# FPGAPower.net
KiCad netlist of a schematic drawn in Altium Designer
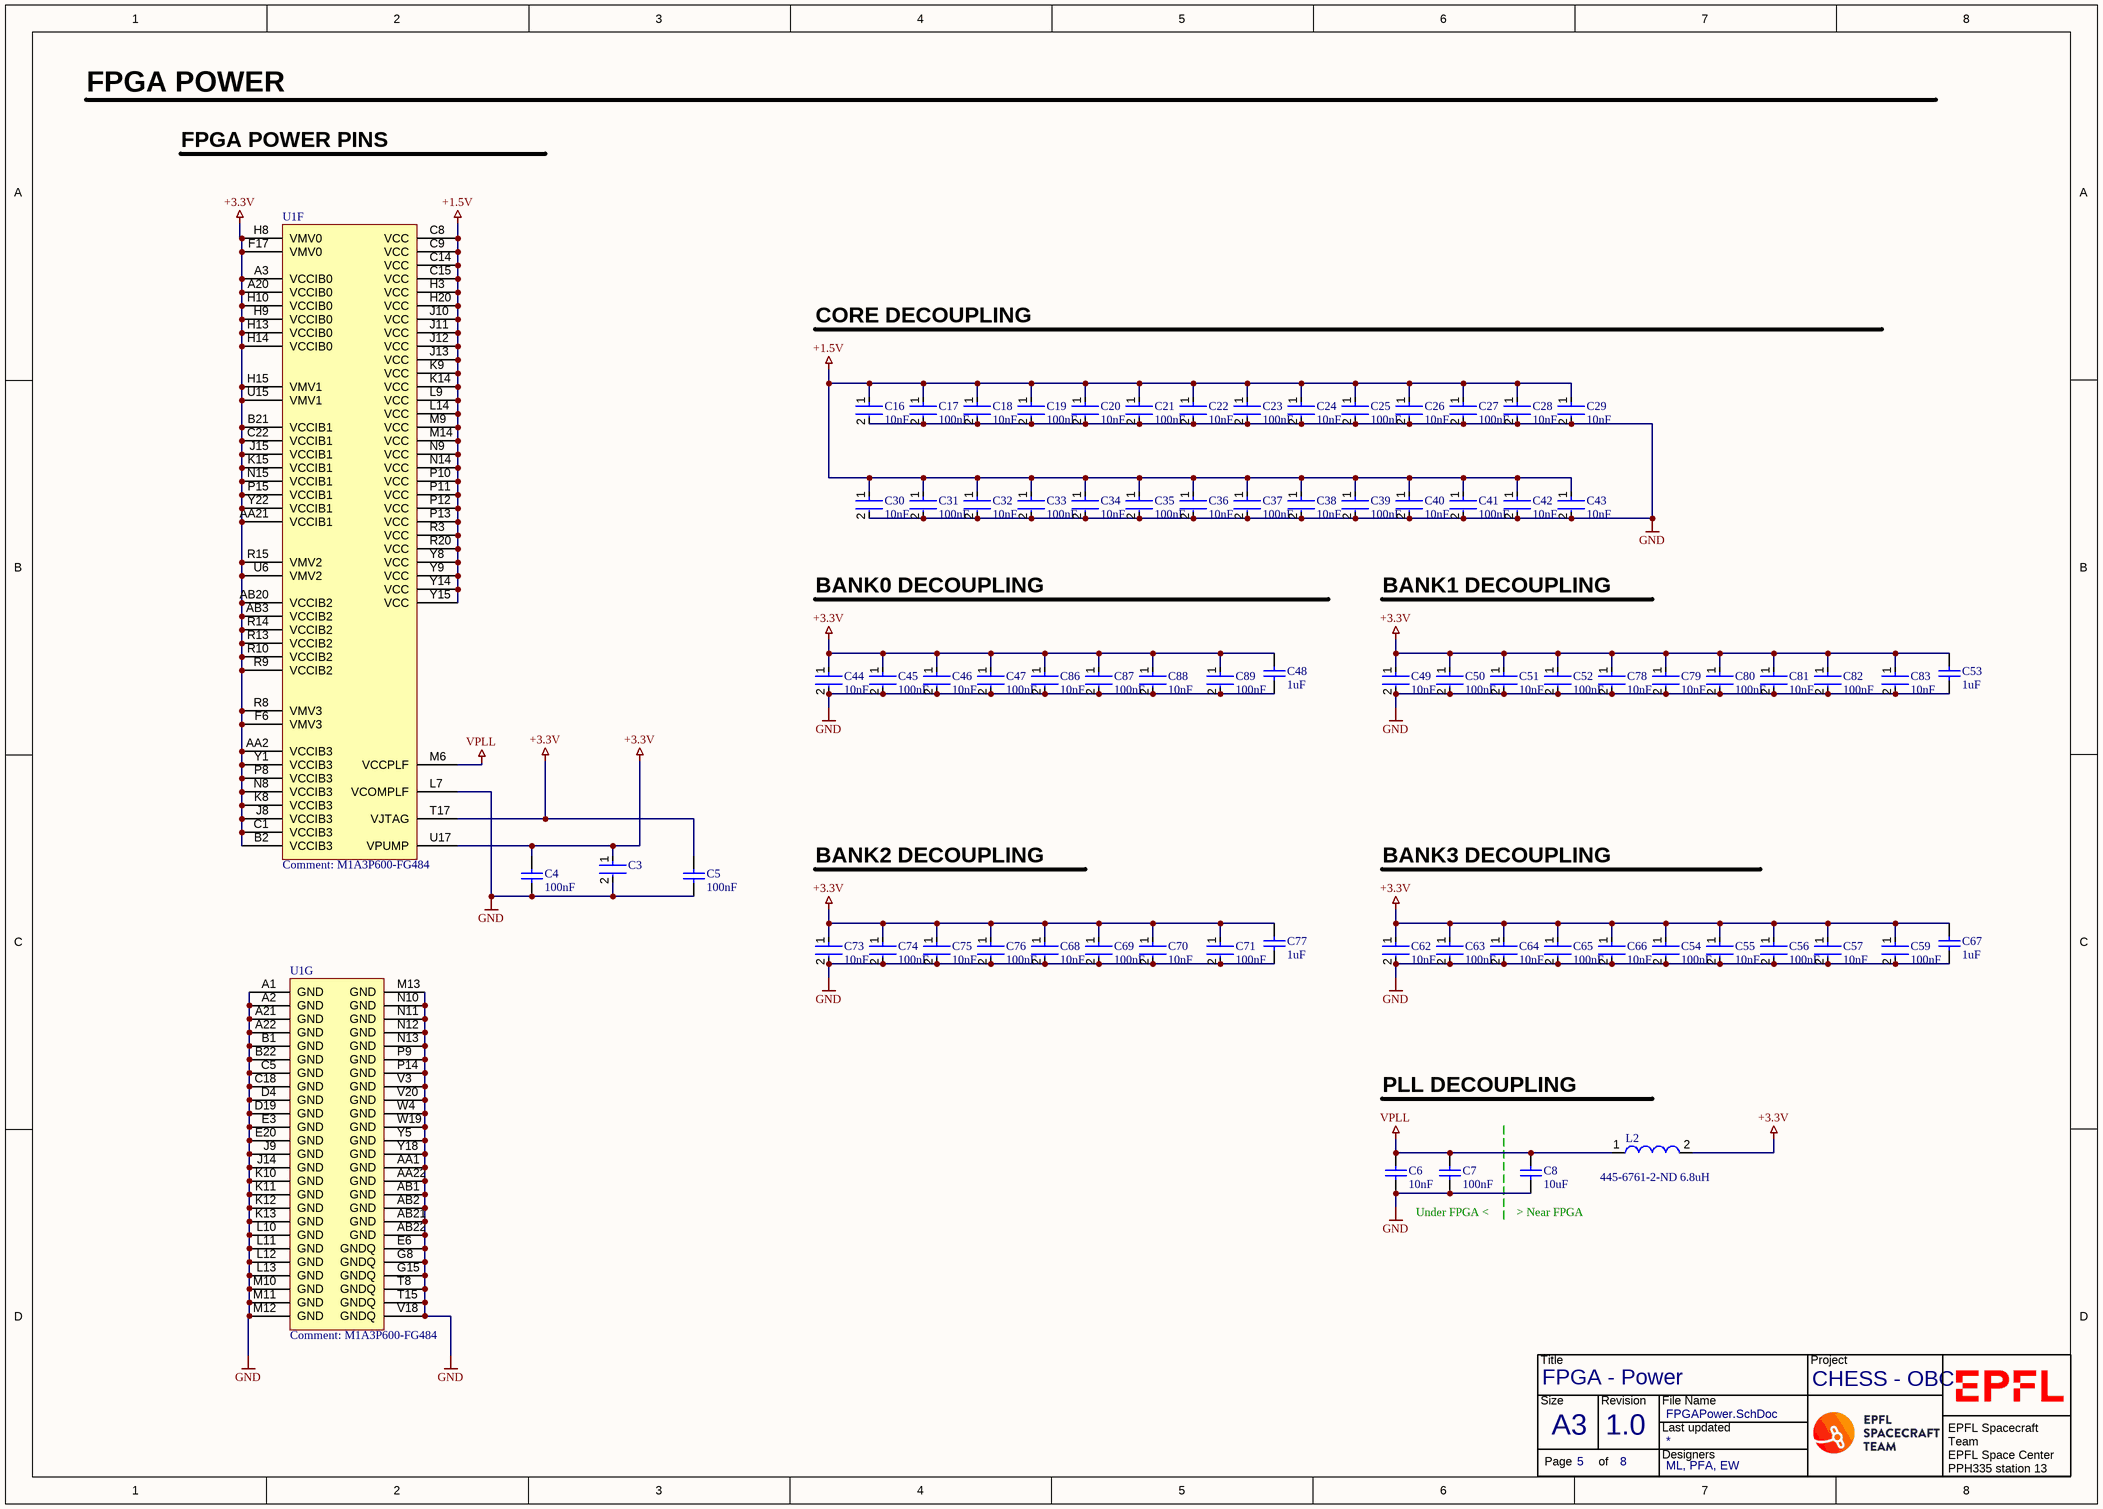
[diagram p0: FPGAPower.SchDoc]

(export (version "E")
  (design (tool "Eeschema 10.0.6"))
  (components
    (comp (ref "C3")
      (value "CC0402KRX5R6BB334")
      (footprint "FP-CC0402-MFG")
      (description "CAP CER 0.33UF 10V X5R 0402")
      (fields
        (field (name "MANUFACTURER") "YAGEO")
        (field (name "OCTOPART") "https://octopart.com/cc0402krx5r6bb334-yageo-21548561")
      )
      (libsource (lib "Altium Content Vault") (part "11868f565c42a9108669ba33697ecf6"))
    )
    (comp (ref "C4")
      (value "100nF")
      (footprint "CAPC1005X60X30ML05T10")
      (fields (field (name "MANUFACTURER") "Kemet") (field (name "PART NUMBER") "C0402C104K8PACTU"))
      (libsource (lib "Altium Content Vault") (part "CAP"))
    )
    (comp (ref "C5")
      (value "100nF")
      (footprint "CAPC1005X60X30ML05T10")
      (fields (field (name "MANUFACTURER") "Kemet") (field (name "PART NUMBER") "C0402C104K8PACTU"))
      (libsource (lib "Altium Content Vault") (part "CAP"))
    )
    (comp (ref "C6")
      (value "10nF")
      (footprint "CAPC0402(1005)60_M")
      (description "CAP 10nF 16V -20% to +80% 0402 (1005 Metric) Thickness 0.6mm SMD")
      (fields (field (name "TOLERANCE") "-20% to +80%"))
      (libsource (lib "Altium Content Vault") (part "CAP"))
    )
    (comp (ref "C7")
      (value "100nF")
      (footprint "CAPC1005X60X30ML05T10")
      (fields (field (name "MANUFACTURER") "Kemet") (field (name "PART NUMBER") "C0402C104K8PACTU"))
      (libsource (lib "Altium Content Vault") (part "CAP"))
    )
    (comp (ref "C8")
      (value "10uF")
      (footprint "CAPC2013X145X20ML20")
      (fields
        (field (name "MANUFACTURER") "TDK")
        (field (name "TOLERANCE") "±10%")
        (field (name "PCN PART NUMBER") "MLCCPartNumberChange30/Nov/2012")
      )
      (libsource (lib "Altium Content Vault") (part "CAP-NP-2"))
    )
    (comp (ref "C16")
      (value "10nF")
      (footprint "FP-GRM155-0_05-IPC_C")
      (fields (field (name "TOLERANCE") "10%") (field (name "VOLTAGE") "25V"))
      (libsource (lib "Altium Content Vault") (part "02cd4be3c70576c341d710602a673aa"))
    )
    (comp (ref "C17")
      (value "100nF")
      (footprint "FP-GRM155-0_05-IPC_C")
      (fields (field (name "TOLERANCE") "10%") (field (name "VOLTAGE") "25V"))
      (libsource (lib "Altium Content Vault") (part "02cd4be3c70576c341d710602a673aa"))
    )
    (comp (ref "C18")
      (value "10nF")
      (footprint "FP-GRM155-0_05-IPC_C")
      (fields (field (name "TOLERANCE") "10%") (field (name "VOLTAGE") "25V"))
      (libsource (lib "Altium Content Vault") (part "02cd4be3c70576c341d710602a673aa"))
    )
    (comp (ref "C19")
      (value "100nF")
      (footprint "FP-GRM155-0_05-IPC_C")
      (fields (field (name "TOLERANCE") "10%") (field (name "VOLTAGE") "25V"))
      (libsource (lib "Altium Content Vault") (part "02cd4be3c70576c341d710602a673aa"))
    )
    (comp (ref "C20")
      (value "10nF")
      (footprint "FP-GRM155-0_05-IPC_C")
      (fields (field (name "TOLERANCE") "10%") (field (name "VOLTAGE") "25V"))
      (libsource (lib "Altium Content Vault") (part "02cd4be3c70576c341d710602a673aa"))
    )
    (comp (ref "C21")
      (value "100nF")
      (footprint "FP-GRM155-0_05-IPC_C")
      (fields (field (name "TOLERANCE") "10%") (field (name "VOLTAGE") "25V"))
      (libsource (lib "Altium Content Vault") (part "02cd4be3c70576c341d710602a673aa"))
    )
    (comp (ref "C22")
      (value "10nF")
      (footprint "FP-GRM155-0_05-IPC_C")
      (fields (field (name "TOLERANCE") "10%") (field (name "VOLTAGE") "25V"))
      (libsource (lib "Altium Content Vault") (part "02cd4be3c70576c341d710602a673aa"))
    )
    (comp (ref "C23")
      (value "100nF")
      (footprint "FP-GRM155-0_05-IPC_C")
      (fields (field (name "TOLERANCE") "10%") (field (name "VOLTAGE") "25V"))
      (libsource (lib "Altium Content Vault") (part "02cd4be3c70576c341d710602a673aa"))
    )
    (comp (ref "C24")
      (value "10nF")
      (footprint "FP-GRM155-0_05-IPC_C")
      (fields (field (name "TOLERANCE") "10%") (field (name "VOLTAGE") "25V"))
      (libsource (lib "Altium Content Vault") (part "02cd4be3c70576c341d710602a673aa"))
    )
    (comp (ref "C25")
      (value "100nF")
      (footprint "FP-GRM155-0_05-IPC_C")
      (fields (field (name "TOLERANCE") "10%") (field (name "VOLTAGE") "25V"))
      (libsource (lib "Altium Content Vault") (part "02cd4be3c70576c341d710602a673aa"))
    )
    (comp (ref "C26")
      (value "10nF")
      (footprint "FP-GRM155-0_05-IPC_C")
      (fields (field (name "TOLERANCE") "10%") (field (name "VOLTAGE") "25V"))
      (libsource (lib "Altium Content Vault") (part "02cd4be3c70576c341d710602a673aa"))
    )
    (comp (ref "C27")
      (value "100nF")
      (footprint "FP-GRM155-0_05-IPC_C")
      (fields (field (name "TOLERANCE") "10%") (field (name "VOLTAGE") "25V"))
      (libsource (lib "Altium Content Vault") (part "02cd4be3c70576c341d710602a673aa"))
    )
    (comp (ref "C28")
      (value "10nF")
      (footprint "FP-GRM155-0_05-IPC_C")
      (fields (field (name "TOLERANCE") "10%") (field (name "VOLTAGE") "25V"))
      (libsource (lib "Altium Content Vault") (part "02cd4be3c70576c341d710602a673aa"))
    )
    (comp (ref "C29")
      (value "10nF")
      (footprint "FP-GRM155-0_05-IPC_C")
      (fields (field (name "TOLERANCE") "10%") (field (name "VOLTAGE") "25V"))
      (libsource (lib "Altium Content Vault") (part "02cd4be3c70576c341d710602a673aa"))
    )
    (comp (ref "C30")
      (value "10nF")
      (footprint "FP-GRM155-0_05-IPC_C")
      (fields (field (name "TOLERANCE") "10%") (field (name "VOLTAGE") "25V"))
      (libsource (lib "Altium Content Vault") (part "02cd4be3c70576c341d710602a673aa"))
    )
    (comp (ref "C31")
      (value "100nF")
      (footprint "FP-GRM155-0_05-IPC_C")
      (fields (field (name "TOLERANCE") "10%") (field (name "VOLTAGE") "25V"))
      (libsource (lib "Altium Content Vault") (part "02cd4be3c70576c341d710602a673aa"))
    )
    (comp (ref "C32")
      (value "10nF")
      (footprint "FP-GRM155-0_05-IPC_C")
      (fields (field (name "TOLERANCE") "10%") (field (name "VOLTAGE") "25V"))
      (libsource (lib "Altium Content Vault") (part "02cd4be3c70576c341d710602a673aa"))
    )
    (comp (ref "C33")
      (value "100nF")
      (footprint "FP-GRM155-0_05-IPC_C")
      (fields (field (name "TOLERANCE") "10%") (field (name "VOLTAGE") "25V"))
      (libsource (lib "Altium Content Vault") (part "02cd4be3c70576c341d710602a673aa"))
    )
    (comp (ref "C34")
      (value "10nF")
      (footprint "FP-GRM155-0_05-IPC_C")
      (fields (field (name "TOLERANCE") "10%") (field (name "VOLTAGE") "25V"))
      (libsource (lib "Altium Content Vault") (part "02cd4be3c70576c341d710602a673aa"))
    )
    (comp (ref "C35")
      (value "100nF")
      (footprint "FP-GRM155-0_05-IPC_C")
      (fields (field (name "TOLERANCE") "10%") (field (name "VOLTAGE") "25V"))
      (libsource (lib "Altium Content Vault") (part "02cd4be3c70576c341d710602a673aa"))
    )
    (comp (ref "C36")
      (value "10nF")
      (footprint "FP-GRM155-0_05-IPC_C")
      (fields (field (name "TOLERANCE") "10%") (field (name "VOLTAGE") "25V"))
      (libsource (lib "Altium Content Vault") (part "02cd4be3c70576c341d710602a673aa"))
    )
    (comp (ref "C37")
      (value "100nF")
      (footprint "FP-GRM155-0_05-IPC_C")
      (fields (field (name "TOLERANCE") "10%") (field (name "VOLTAGE") "25V"))
      (libsource (lib "Altium Content Vault") (part "02cd4be3c70576c341d710602a673aa"))
    )
    (comp (ref "C38")
      (value "10nF")
      (footprint "FP-GRM155-0_05-IPC_C")
      (fields (field (name "TOLERANCE") "10%") (field (name "VOLTAGE") "25V"))
      (libsource (lib "Altium Content Vault") (part "02cd4be3c70576c341d710602a673aa"))
    )
    (comp (ref "C39")
      (value "100nF")
      (footprint "FP-GRM155-0_05-IPC_C")
      (fields (field (name "TOLERANCE") "10%") (field (name "VOLTAGE") "25V"))
      (libsource (lib "Altium Content Vault") (part "02cd4be3c70576c341d710602a673aa"))
    )
    (comp (ref "C40")
      (value "10nF")
      (footprint "FP-GRM155-0_05-IPC_C")
      (fields (field (name "TOLERANCE") "10%") (field (name "VOLTAGE") "25V"))
      (libsource (lib "Altium Content Vault") (part "02cd4be3c70576c341d710602a673aa"))
    )
    (comp (ref "C41")
      (value "100nF")
      (footprint "FP-GRM155-0_05-IPC_C")
      (fields (field (name "TOLERANCE") "10%") (field (name "VOLTAGE") "25V"))
      (libsource (lib "Altium Content Vault") (part "02cd4be3c70576c341d710602a673aa"))
    )
    (comp (ref "C42")
      (value "10nF")
      (footprint "FP-GRM155-0_05-IPC_C")
      (fields (field (name "TOLERANCE") "10%") (field (name "VOLTAGE") "25V"))
      (libsource (lib "Altium Content Vault") (part "02cd4be3c70576c341d710602a673aa"))
    )
    (comp (ref "C43")
      (value "10nF")
      (footprint "FP-GRM155-0_05-IPC_C")
      (fields (field (name "TOLERANCE") "10%") (field (name "VOLTAGE") "25V"))
      (libsource (lib "Altium Content Vault") (part "02cd4be3c70576c341d710602a673aa"))
    )
    (comp (ref "C44")
      (value "10nF")
      (footprint "FP-GRM155-0_05-IPC_C")
      (fields (field (name "TOLERANCE") "10%") (field (name "VOLTAGE") "25V"))
      (libsource (lib "Altium Content Vault") (part "02cd4be3c70576c341d710602a673aa"))
    )
    (comp (ref "C45")
      (value "100nF")
      (footprint "FP-GRM155-0_05-IPC_C")
      (fields (field (name "TOLERANCE") "10%") (field (name "VOLTAGE") "25V"))
      (libsource (lib "Altium Content Vault") (part "02cd4be3c70576c341d710602a673aa"))
    )
    (comp (ref "C46")
      (value "10nF")
      (footprint "FP-GRM155-0_05-IPC_C")
      (fields (field (name "TOLERANCE") "10%") (field (name "VOLTAGE") "25V"))
      (libsource (lib "Altium Content Vault") (part "02cd4be3c70576c341d710602a673aa"))
    )
    (comp (ref "C47")
      (value "100nF")
      (footprint "FP-GRM155-0_05-IPC_C")
      (fields (field (name "TOLERANCE") "10%") (field (name "VOLTAGE") "25V"))
      (libsource (lib "Altium Content Vault") (part "02cd4be3c70576c341d710602a673aa"))
    )
    (comp (ref "C48")
      (value "1uF")
      (footprint "CAPC1608X90X20LL10")
      (description "Chip Capacitor, 1 uF, +/- 10%, 50 V, -55 to 85 degC, 0603 (1608 Metric), RoHS, Tape and Reel")
      (fields
        (field (name "MANUFACTURER") "TDK")
        (field (name "PCN PART NUMBER") "MLCCPartNumberChange30/Nov/2012")
      )
      (libsource (lib "Altium Content Vault") (part "CAP-NP-2"))
    )
    (comp (ref "C49")
      (value "10nF")
      (footprint "FP-GRM155-0_05-IPC_C")
      (fields (field (name "TOLERANCE") "10%") (field (name "VOLTAGE") "25V"))
      (libsource (lib "Altium Content Vault") (part "02cd4be3c70576c341d710602a673aa"))
    )
    (comp (ref "C50")
      (value "100nF")
      (footprint "FP-GRM155-0_05-IPC_C")
      (fields (field (name "TOLERANCE") "10%") (field (name "VOLTAGE") "25V"))
      (libsource (lib "Altium Content Vault") (part "02cd4be3c70576c341d710602a673aa"))
    )
    (comp (ref "C51")
      (value "10nF")
      (footprint "FP-GRM155-0_05-IPC_C")
      (fields (field (name "TOLERANCE") "10%") (field (name "VOLTAGE") "25V"))
      (libsource (lib "Altium Content Vault") (part "02cd4be3c70576c341d710602a673aa"))
    )
    (comp (ref "C52")
      (value "100nF")
      (footprint "FP-GRM155-0_05-IPC_C")
      (fields (field (name "TOLERANCE") "10%") (field (name "VOLTAGE") "25V"))
      (libsource (lib "Altium Content Vault") (part "02cd4be3c70576c341d710602a673aa"))
    )
    (comp (ref "C53")
      (value "1uF")
      (footprint "CAPC1608X90X20LL10")
      (description "Chip Capacitor, 1 uF, +/- 10%, 50 V, -55 to 85 degC, 0603 (1608 Metric), RoHS, Tape and Reel")
      (fields
        (field (name "MANUFACTURER") "TDK")
        (field (name "PCN PART NUMBER") "MLCCPartNumberChange30/Nov/2012")
      )
      (libsource (lib "Altium Content Vault") (part "CAP-NP-2"))
    )
    (comp (ref "C54")
      (value "100nF")
      (footprint "FP-GRM155-0_05-IPC_C")
      (fields (field (name "TOLERANCE") "10%") (field (name "VOLTAGE") "25V"))
      (libsource (lib "Altium Content Vault") (part "02cd4be3c70576c341d710602a673aa"))
    )
    (comp (ref "C55")
      (value "10nF")
      (footprint "FP-GRM155-0_05-IPC_C")
      (fields (field (name "TOLERANCE") "10%") (field (name "VOLTAGE") "25V"))
      (libsource (lib "Altium Content Vault") (part "02cd4be3c70576c341d710602a673aa"))
    )
    (comp (ref "C56")
      (value "100nF")
      (footprint "FP-GRM155-0_05-IPC_C")
      (fields (field (name "TOLERANCE") "10%") (field (name "VOLTAGE") "25V"))
      (libsource (lib "Altium Content Vault") (part "02cd4be3c70576c341d710602a673aa"))
    )
    (comp (ref "C57")
      (value "10nF")
      (footprint "FP-GRM155-0_05-IPC_C")
      (fields (field (name "TOLERANCE") "10%") (field (name "VOLTAGE") "25V"))
      (libsource (lib "Altium Content Vault") (part "02cd4be3c70576c341d710602a673aa"))
    )
    (comp (ref "C59")
      (value "100nF")
      (footprint "FP-GRM155-0_05-IPC_C")
      (fields (field (name "TOLERANCE") "10%") (field (name "VOLTAGE") "25V"))
      (libsource (lib "Altium Content Vault") (part "02cd4be3c70576c341d710602a673aa"))
    )
    (comp (ref "C62")
      (value "10nF")
      (footprint "FP-GRM155-0_05-IPC_C")
      (fields (field (name "TOLERANCE") "10%") (field (name "VOLTAGE") "25V"))
      (libsource (lib "Altium Content Vault") (part "02cd4be3c70576c341d710602a673aa"))
    )
    (comp (ref "C63")
      (value "100nF")
      (footprint "FP-GRM155-0_05-IPC_C")
      (fields (field (name "TOLERANCE") "10%") (field (name "VOLTAGE") "25V"))
      (libsource (lib "Altium Content Vault") (part "02cd4be3c70576c341d710602a673aa"))
    )
    (comp (ref "C64")
      (value "10nF")
      (footprint "FP-GRM155-0_05-IPC_C")
      (fields (field (name "TOLERANCE") "10%") (field (name "VOLTAGE") "25V"))
      (libsource (lib "Altium Content Vault") (part "02cd4be3c70576c341d710602a673aa"))
    )
    (comp (ref "C65")
      (value "100nF")
      (footprint "FP-GRM155-0_05-IPC_C")
      (fields (field (name "TOLERANCE") "10%") (field (name "VOLTAGE") "25V"))
      (libsource (lib "Altium Content Vault") (part "02cd4be3c70576c341d710602a673aa"))
    )
    (comp (ref "C66")
      (value "10nF")
      (footprint "FP-GRM155-0_05-IPC_C")
      (fields (field (name "TOLERANCE") "10%") (field (name "VOLTAGE") "25V"))
      (libsource (lib "Altium Content Vault") (part "02cd4be3c70576c341d710602a673aa"))
    )
    (comp (ref "C67")
      (value "1uF")
      (footprint "CAPC1608X90X20LL10")
      (description "Chip Capacitor, 1 uF, +/- 10%, 50 V, -55 to 85 degC, 0603 (1608 Metric), RoHS, Tape and Reel")
      (fields
        (field (name "MANUFACTURER") "TDK")
        (field (name "PCN PART NUMBER") "MLCCPartNumberChange30/Nov/2012")
      )
      (libsource (lib "Altium Content Vault") (part "CAP-NP-2"))
    )
    (comp (ref "C68")
      (value "10nF")
      (footprint "FP-GRM155-0_05-IPC_C")
      (fields (field (name "TOLERANCE") "10%") (field (name "VOLTAGE") "25V"))
      (libsource (lib "Altium Content Vault") (part "02cd4be3c70576c341d710602a673aa"))
    )
    (comp (ref "C69")
      (value "100nF")
      (footprint "FP-GRM155-0_05-IPC_C")
      (fields (field (name "TOLERANCE") "10%") (field (name "VOLTAGE") "25V"))
      (libsource (lib "Altium Content Vault") (part "02cd4be3c70576c341d710602a673aa"))
    )
    (comp (ref "C70")
      (value "10nF")
      (footprint "FP-GRM155-0_05-IPC_C")
      (fields (field (name "TOLERANCE") "10%") (field (name "VOLTAGE") "25V"))
      (libsource (lib "Altium Content Vault") (part "02cd4be3c70576c341d710602a673aa"))
    )
    (comp (ref "C71")
      (value "100nF")
      (footprint "FP-GRM155-0_05-IPC_C")
      (fields (field (name "TOLERANCE") "10%") (field (name "VOLTAGE") "25V"))
      (libsource (lib "Altium Content Vault") (part "02cd4be3c70576c341d710602a673aa"))
    )
    (comp (ref "C73")
      (value "10nF")
      (footprint "FP-GRM155-0_05-IPC_C")
      (fields (field (name "TOLERANCE") "10%") (field (name "VOLTAGE") "25V"))
      (libsource (lib "Altium Content Vault") (part "02cd4be3c70576c341d710602a673aa"))
    )
    (comp (ref "C74")
      (value "100nF")
      (footprint "FP-GRM155-0_05-IPC_C")
      (fields (field (name "TOLERANCE") "10%") (field (name "VOLTAGE") "25V"))
      (libsource (lib "Altium Content Vault") (part "02cd4be3c70576c341d710602a673aa"))
    )
    (comp (ref "C75")
      (value "10nF")
      (footprint "FP-GRM155-0_05-IPC_C")
      (fields (field (name "TOLERANCE") "10%") (field (name "VOLTAGE") "25V"))
      (libsource (lib "Altium Content Vault") (part "02cd4be3c70576c341d710602a673aa"))
    )
    (comp (ref "C76")
      (value "100nF")
      (footprint "FP-GRM155-0_05-IPC_C")
      (fields (field (name "TOLERANCE") "10%") (field (name "VOLTAGE") "25V"))
      (libsource (lib "Altium Content Vault") (part "02cd4be3c70576c341d710602a673aa"))
    )
    (comp (ref "C77")
      (value "1uF")
      (footprint "CAPC1608X90X20LL10")
      (description "Chip Capacitor, 1 uF, +/- 10%, 50 V, -55 to 85 degC, 0603 (1608 Metric), RoHS, Tape and Reel")
      (fields
        (field (name "MANUFACTURER") "TDK")
        (field (name "PCN PART NUMBER") "MLCCPartNumberChange30/Nov/2012")
      )
      (libsource (lib "Altium Content Vault") (part "CAP-NP-2"))
    )
    (comp (ref "C78")
      (value "10nF")
      (footprint "FP-GRM155-0_05-IPC_C")
      (fields (field (name "TOLERANCE") "10%") (field (name "VOLTAGE") "25V"))
      (libsource (lib "Altium Content Vault") (part "02cd4be3c70576c341d710602a673aa"))
    )
    (comp (ref "C79")
      (value "10nF")
      (footprint "FP-GRM155-0_05-IPC_C")
      (fields (field (name "TOLERANCE") "10%") (field (name "VOLTAGE") "25V"))
      (libsource (lib "Altium Content Vault") (part "02cd4be3c70576c341d710602a673aa"))
    )
    (comp (ref "C80")
      (value "100nF")
      (footprint "FP-GRM155-0_05-IPC_C")
      (fields (field (name "TOLERANCE") "10%") (field (name "VOLTAGE") "25V"))
      (libsource (lib "Altium Content Vault") (part "02cd4be3c70576c341d710602a673aa"))
    )
    (comp (ref "C81")
      (value "10nF")
      (footprint "FP-GRM155-0_05-IPC_C")
      (fields (field (name "TOLERANCE") "10%") (field (name "VOLTAGE") "25V"))
      (libsource (lib "Altium Content Vault") (part "02cd4be3c70576c341d710602a673aa"))
    )
    (comp (ref "C82")
      (value "100nF")
      (footprint "FP-GRM155-0_05-IPC_C")
      (fields (field (name "TOLERANCE") "10%") (field (name "VOLTAGE") "25V"))
      (libsource (lib "Altium Content Vault") (part "02cd4be3c70576c341d710602a673aa"))
    )
    (comp (ref "C83")
      (value "10nF")
      (footprint "FP-GRM155-0_05-IPC_C")
      (fields (field (name "TOLERANCE") "10%") (field (name "VOLTAGE") "25V"))
      (libsource (lib "Altium Content Vault") (part "02cd4be3c70576c341d710602a673aa"))
    )
    (comp (ref "C86")
      (value "10nF")
      (footprint "FP-GRM155-0_05-IPC_C")
      (fields (field (name "TOLERANCE") "10%") (field (name "VOLTAGE") "25V"))
      (libsource (lib "Altium Content Vault") (part "02cd4be3c70576c341d710602a673aa"))
    )
    (comp (ref "C87")
      (value "100nF")
      (footprint "FP-GRM155-0_05-IPC_C")
      (fields (field (name "TOLERANCE") "10%") (field (name "VOLTAGE") "25V"))
      (libsource (lib "Altium Content Vault") (part "02cd4be3c70576c341d710602a673aa"))
    )
    (comp (ref "C88")
      (value "10nF")
      (footprint "FP-GRM155-0_05-IPC_C")
      (fields (field (name "TOLERANCE") "10%") (field (name "VOLTAGE") "25V"))
      (libsource (lib "Altium Content Vault") (part "02cd4be3c70576c341d710602a673aa"))
    )
    (comp (ref "C89")
      (value "100nF")
      (footprint "FP-GRM155-0_05-IPC_C")
      (fields (field (name "TOLERANCE") "10%") (field (name "VOLTAGE") "25V"))
      (libsource (lib "Altium Content Vault") (part "02cd4be3c70576c341d710602a673aa"))
    )
    (comp (ref "L2")
      (value "445-6761-2-ND 6.8uH")
      (footprint "SMD-0805")
      (description "SMD-Multilayer Inductor WE-MI, L = 1.00 µH")
      (libsource (lib "Altium Content Vault") (part "PAS-IND-INDUCTOR-2"))
    )
    (comp (ref "U1")
      (value "M1A3P600-FG484")
      (footprint "FG484")
      (libsource (lib "Altium Content Vault") (part "FPGA-ACTPA3-A3P600-GA484"))
    )
  )
  (nets
    (net (code "1") (name "+1.5V") (class "Default")
      (node (ref "C16") (pin "1") (pinfunction "1_1") (pintype "passive"))
      (node (ref "C17") (pin "1") (pinfunction "1_1") (pintype "passive"))
      (node (ref "C18") (pin "1") (pinfunction "1_1") (pintype "passive"))
      (node (ref "C19") (pin "1") (pinfunction "1_1") (pintype "passive"))
      (node (ref "C20") (pin "1") (pinfunction "1_1") (pintype "passive"))
      (node (ref "C21") (pin "1") (pinfunction "1_1") (pintype "passive"))
      (node (ref "C22") (pin "1") (pinfunction "1_1") (pintype "passive"))
      (node (ref "C23") (pin "1") (pinfunction "1_1") (pintype "passive"))
      (node (ref "C24") (pin "1") (pinfunction "1_1") (pintype "passive"))
      (node (ref "C25") (pin "1") (pinfunction "1_1") (pintype "passive"))
      (node (ref "C26") (pin "1") (pinfunction "1_1") (pintype "passive"))
      (node (ref "C27") (pin "1") (pinfunction "1_1") (pintype "passive"))
      (node (ref "C28") (pin "1") (pinfunction "1_1") (pintype "passive"))
      (node (ref "C29") (pin "1") (pinfunction "1_1") (pintype "passive"))
      (node (ref "C30") (pin "1") (pinfunction "1_1") (pintype "passive"))
      (node (ref "C31") (pin "1") (pinfunction "1_1") (pintype "passive"))
      (node (ref "C32") (pin "1") (pinfunction "1_1") (pintype "passive"))
      (node (ref "C33") (pin "1") (pinfunction "1_1") (pintype "passive"))
      (node (ref "C34") (pin "1") (pinfunction "1_1") (pintype "passive"))
      (node (ref "C35") (pin "1") (pinfunction "1_1") (pintype "passive"))
      (node (ref "C36") (pin "1") (pinfunction "1_1") (pintype "passive"))
      (node (ref "C37") (pin "1") (pinfunction "1_1") (pintype "passive"))
      (node (ref "C38") (pin "1") (pinfunction "1_1") (pintype "passive"))
      (node (ref "C39") (pin "1") (pinfunction "1_1") (pintype "passive"))
      (node (ref "C40") (pin "1") (pinfunction "1_1") (pintype "passive"))
      (node (ref "C41") (pin "1") (pinfunction "1_1") (pintype "passive"))
      (node (ref "C42") (pin "1") (pinfunction "1_1") (pintype "passive"))
      (node (ref "C43") (pin "1") (pinfunction "1_1") (pintype "passive"))
      (node (ref "U1") (pin "C14") (pinfunction "VCC_C14") (pintype "power_in"))
      (node (ref "U1") (pin "C15") (pinfunction "VCC_C15") (pintype "power_in"))
      (node (ref "U1") (pin "C8") (pinfunction "VCC_C8") (pintype "power_in"))
      (node (ref "U1") (pin "C9") (pinfunction "VCC_C9") (pintype "power_in"))
      (node (ref "U1") (pin "H20") (pinfunction "VCC_H20") (pintype "power_in"))
      (node (ref "U1") (pin "H3") (pinfunction "VCC_H3") (pintype "power_in"))
      (node (ref "U1") (pin "J10") (pinfunction "VCC_J10") (pintype "power_in"))
      (node (ref "U1") (pin "J11") (pinfunction "VCC_J11") (pintype "power_in"))
      (node (ref "U1") (pin "J12") (pinfunction "VCC_J12") (pintype "power_in"))
      (node (ref "U1") (pin "J13") (pinfunction "VCC_J13") (pintype "power_in"))
      (node (ref "U1") (pin "K14") (pinfunction "VCC_K14") (pintype "power_in"))
      (node (ref "U1") (pin "K9") (pinfunction "VCC_K9") (pintype "power_in"))
      (node (ref "U1") (pin "L14") (pinfunction "VCC_L14") (pintype "power_in"))
      (node (ref "U1") (pin "L9") (pinfunction "VCC_L9") (pintype "power_in"))
      (node (ref "U1") (pin "M14") (pinfunction "VCC_M14") (pintype "power_in"))
      (node (ref "U1") (pin "M9") (pinfunction "VCC_M9") (pintype "power_in"))
      (node (ref "U1") (pin "N14") (pinfunction "VCC_N14") (pintype "power_in"))
      (node (ref "U1") (pin "N9") (pinfunction "VCC_N9") (pintype "power_in"))
      (node (ref "U1") (pin "P10") (pinfunction "VCC_P10") (pintype "power_in"))
      (node (ref "U1") (pin "P11") (pinfunction "VCC_P11") (pintype "power_in"))
      (node (ref "U1") (pin "P12") (pinfunction "VCC_P12") (pintype "power_in"))
      (node (ref "U1") (pin "P13") (pinfunction "VCC_P13") (pintype "power_in"))
      (node (ref "U1") (pin "R20") (pinfunction "VCC_R20") (pintype "power_in"))
      (node (ref "U1") (pin "R3") (pinfunction "VCC_R3") (pintype "power_in"))
      (node (ref "U1") (pin "Y14") (pinfunction "VCC_Y14") (pintype "power_in"))
      (node (ref "U1") (pin "Y15") (pinfunction "VCC_Y15") (pintype "power_in"))
      (node (ref "U1") (pin "Y8") (pinfunction "VCC_Y8") (pintype "power_in"))
      (node (ref "U1") (pin "Y9") (pinfunction "VCC_Y9") (pintype "power_in"))
    )
    (net (code "2") (name "+3.3V") (class "Default")
      (node (ref "C3") (pin "1") (pinfunction "1_1") (pintype "passive"))
      (node (ref "C4") (pin "2") (pinfunction "2_2") (pintype "passive"))
      (node (ref "C44") (pin "1") (pinfunction "1_1") (pintype "passive"))
      (node (ref "C45") (pin "1") (pinfunction "1_1") (pintype "passive"))
      (node (ref "C46") (pin "1") (pinfunction "1_1") (pintype "passive"))
      (node (ref "C47") (pin "1") (pinfunction "1_1") (pintype "passive"))
      (node (ref "C48") (pin "2") (pinfunction "2_2") (pintype "passive"))
      (node (ref "C49") (pin "1") (pinfunction "1_1") (pintype "passive"))
      (node (ref "C5") (pin "2") (pinfunction "2_2") (pintype "passive"))
      (node (ref "C50") (pin "1") (pinfunction "1_1") (pintype "passive"))
      (node (ref "C51") (pin "1") (pinfunction "1_1") (pintype "passive"))
      (node (ref "C52") (pin "1") (pinfunction "1_1") (pintype "passive"))
      (node (ref "C53") (pin "2") (pinfunction "2_2") (pintype "passive"))
      (node (ref "C54") (pin "1") (pinfunction "1_1") (pintype "passive"))
      (node (ref "C55") (pin "1") (pinfunction "1_1") (pintype "passive"))
      (node (ref "C56") (pin "1") (pinfunction "1_1") (pintype "passive"))
      (node (ref "C57") (pin "1") (pinfunction "1_1") (pintype "passive"))
      (node (ref "C59") (pin "1") (pinfunction "1_1") (pintype "passive"))
      (node (ref "C62") (pin "1") (pinfunction "1_1") (pintype "passive"))
      (node (ref "C63") (pin "1") (pinfunction "1_1") (pintype "passive"))
      (node (ref "C64") (pin "1") (pinfunction "1_1") (pintype "passive"))
      (node (ref "C65") (pin "1") (pinfunction "1_1") (pintype "passive"))
      (node (ref "C66") (pin "1") (pinfunction "1_1") (pintype "passive"))
      (node (ref "C67") (pin "2") (pinfunction "2_2") (pintype "passive"))
      (node (ref "C68") (pin "1") (pinfunction "1_1") (pintype "passive"))
      (node (ref "C69") (pin "1") (pinfunction "1_1") (pintype "passive"))
      (node (ref "C70") (pin "1") (pinfunction "1_1") (pintype "passive"))
      (node (ref "C71") (pin "1") (pinfunction "1_1") (pintype "passive"))
      (node (ref "C73") (pin "1") (pinfunction "1_1") (pintype "passive"))
      (node (ref "C74") (pin "1") (pinfunction "1_1") (pintype "passive"))
      (node (ref "C75") (pin "1") (pinfunction "1_1") (pintype "passive"))
      (node (ref "C76") (pin "1") (pinfunction "1_1") (pintype "passive"))
      (node (ref "C77") (pin "2") (pinfunction "2_2") (pintype "passive"))
      (node (ref "C78") (pin "1") (pinfunction "1_1") (pintype "passive"))
      (node (ref "C79") (pin "1") (pinfunction "1_1") (pintype "passive"))
      (node (ref "C80") (pin "1") (pinfunction "1_1") (pintype "passive"))
      (node (ref "C81") (pin "1") (pinfunction "1_1") (pintype "passive"))
      (node (ref "C82") (pin "1") (pinfunction "1_1") (pintype "passive"))
      (node (ref "C83") (pin "1") (pinfunction "1_1") (pintype "passive"))
      (node (ref "C86") (pin "1") (pinfunction "1_1") (pintype "passive"))
      (node (ref "C87") (pin "1") (pinfunction "1_1") (pintype "passive"))
      (node (ref "C88") (pin "1") (pinfunction "1_1") (pintype "passive"))
      (node (ref "C89") (pin "1") (pinfunction "1_1") (pintype "passive"))
      (node (ref "L2") (pin "2") (pinfunction "2_2") (pintype "passive"))
      (node (ref "U1") (pin "A20") (pinfunction "VCCIB0_A20") (pintype "power_in"))
      (node (ref "U1") (pin "A3") (pinfunction "VCCIB0_A3") (pintype "power_in"))
      (node (ref "U1") (pin "AA2") (pinfunction "VCCIB3_AA2") (pintype "power_in"))
      (node (ref "U1") (pin "AA21") (pinfunction "VCCIB1_AA21") (pintype "power_in"))
      (node (ref "U1") (pin "AB20") (pinfunction "VCCIB2_AB20") (pintype "power_in"))
      (node (ref "U1") (pin "AB3") (pinfunction "VCCIB2_AB3") (pintype "power_in"))
      (node (ref "U1") (pin "B2") (pinfunction "VCCIB3_B2") (pintype "power_in"))
      (node (ref "U1") (pin "B21") (pinfunction "VCCIB1_B21") (pintype "power_in"))
      (node (ref "U1") (pin "C1") (pinfunction "VCCIB3_C1") (pintype "power_in"))
      (node (ref "U1") (pin "C22") (pinfunction "VCCIB1_C22") (pintype "power_in"))
      (node (ref "U1") (pin "F17") (pinfunction "VMV0_F17") (pintype "power_in"))
      (node (ref "U1") (pin "F6") (pinfunction "VMV3_F6") (pintype "power_in"))
      (node (ref "U1") (pin "H10") (pinfunction "VCCIB0_H10") (pintype "power_in"))
      (node (ref "U1") (pin "H13") (pinfunction "VCCIB0_H13") (pintype "power_in"))
      (node (ref "U1") (pin "H14") (pinfunction "VCCIB0_H14") (pintype "power_in"))
      (node (ref "U1") (pin "H15") (pinfunction "VMV1_H15") (pintype "power_in"))
      (node (ref "U1") (pin "H8") (pinfunction "VMV0_H8") (pintype "power_in"))
      (node (ref "U1") (pin "H9") (pinfunction "VCCIB0_H9") (pintype "power_in"))
      (node (ref "U1") (pin "J15") (pinfunction "VCCIB1_J15") (pintype "power_in"))
      (node (ref "U1") (pin "J8") (pinfunction "VCCIB3_J8") (pintype "power_in"))
      (node (ref "U1") (pin "K15") (pinfunction "VCCIB1_K15") (pintype "power_in"))
      (node (ref "U1") (pin "K8") (pinfunction "VCCIB3_K8") (pintype "power_in"))
      (node (ref "U1") (pin "N15") (pinfunction "VCCIB1_N15") (pintype "power_in"))
      (node (ref "U1") (pin "N8") (pinfunction "VCCIB3_N8") (pintype "power_in"))
      (node (ref "U1") (pin "P15") (pinfunction "VCCIB1_P15") (pintype "power_in"))
      (node (ref "U1") (pin "P8") (pinfunction "VCCIB3_P8") (pintype "power_in"))
      (node (ref "U1") (pin "R10") (pinfunction "VCCIB2_R10") (pintype "power_in"))
      (node (ref "U1") (pin "R13") (pinfunction "VCCIB2_R13") (pintype "power_in"))
      (node (ref "U1") (pin "R14") (pinfunction "VCCIB2_R14") (pintype "power_in"))
      (node (ref "U1") (pin "R15") (pinfunction "VMV2_R15") (pintype "power_in"))
      (node (ref "U1") (pin "R8") (pinfunction "VMV3_R8") (pintype "power_in"))
      (node (ref "U1") (pin "R9") (pinfunction "VCCIB2_R9") (pintype "power_in"))
      (node (ref "U1") (pin "T17") (pinfunction "VJTAG_T17") (pintype "power_in"))
      (node (ref "U1") (pin "U15") (pinfunction "VMV1_U15") (pintype "power_in"))
      (node (ref "U1") (pin "U17") (pinfunction "VPUMP_U17") (pintype "power_in"))
      (node (ref "U1") (pin "U6") (pinfunction "VMV2_U6") (pintype "power_in"))
      (node (ref "U1") (pin "Y1") (pinfunction "VCCIB3_Y1") (pintype "power_in"))
      (node (ref "U1") (pin "Y22") (pinfunction "VCCIB1_Y22") (pintype "power_in"))
    )
    (net (code "3") (name "GND") (class "Default")
      (node (ref "C16") (pin "2") (pinfunction "2_2") (pintype "passive"))
      (node (ref "C17") (pin "2") (pinfunction "2_2") (pintype "passive"))
      (node (ref "C18") (pin "2") (pinfunction "2_2") (pintype "passive"))
      (node (ref "C19") (pin "2") (pinfunction "2_2") (pintype "passive"))
      (node (ref "C20") (pin "2") (pinfunction "2_2") (pintype "passive"))
      (node (ref "C21") (pin "2") (pinfunction "2_2") (pintype "passive"))
      (node (ref "C22") (pin "2") (pinfunction "2_2") (pintype "passive"))
      (node (ref "C23") (pin "2") (pinfunction "2_2") (pintype "passive"))
      (node (ref "C24") (pin "2") (pinfunction "2_2") (pintype "passive"))
      (node (ref "C25") (pin "2") (pinfunction "2_2") (pintype "passive"))
      (node (ref "C26") (pin "2") (pinfunction "2_2") (pintype "passive"))
      (node (ref "C27") (pin "2") (pinfunction "2_2") (pintype "passive"))
      (node (ref "C28") (pin "2") (pinfunction "2_2") (pintype "passive"))
      (node (ref "C29") (pin "2") (pinfunction "2_2") (pintype "passive"))
      (node (ref "C3") (pin "2") (pinfunction "2_2") (pintype "passive"))
      (node (ref "C30") (pin "2") (pinfunction "2_2") (pintype "passive"))
      (node (ref "C31") (pin "2") (pinfunction "2_2") (pintype "passive"))
      (node (ref "C32") (pin "2") (pinfunction "2_2") (pintype "passive"))
      (node (ref "C33") (pin "2") (pinfunction "2_2") (pintype "passive"))
      (node (ref "C34") (pin "2") (pinfunction "2_2") (pintype "passive"))
      (node (ref "C35") (pin "2") (pinfunction "2_2") (pintype "passive"))
      (node (ref "C36") (pin "2") (pinfunction "2_2") (pintype "passive"))
      (node (ref "C37") (pin "2") (pinfunction "2_2") (pintype "passive"))
      (node (ref "C38") (pin "2") (pinfunction "2_2") (pintype "passive"))
      (node (ref "C39") (pin "2") (pinfunction "2_2") (pintype "passive"))
      (node (ref "C4") (pin "1") (pinfunction "1_1") (pintype "passive"))
      (node (ref "C40") (pin "2") (pinfunction "2_2") (pintype "passive"))
      (node (ref "C41") (pin "2") (pinfunction "2_2") (pintype "passive"))
      (node (ref "C42") (pin "2") (pinfunction "2_2") (pintype "passive"))
      (node (ref "C43") (pin "2") (pinfunction "2_2") (pintype "passive"))
      (node (ref "C44") (pin "2") (pinfunction "2_2") (pintype "passive"))
      (node (ref "C45") (pin "2") (pinfunction "2_2") (pintype "passive"))
      (node (ref "C46") (pin "2") (pinfunction "2_2") (pintype "passive"))
      (node (ref "C47") (pin "2") (pinfunction "2_2") (pintype "passive"))
      (node (ref "C48") (pin "1") (pinfunction "1_1") (pintype "passive"))
      (node (ref "C49") (pin "2") (pinfunction "2_2") (pintype "passive"))
      (node (ref "C5") (pin "1") (pinfunction "1_1") (pintype "passive"))
      (node (ref "C50") (pin "2") (pinfunction "2_2") (pintype "passive"))
      (node (ref "C51") (pin "2") (pinfunction "2_2") (pintype "passive"))
      (node (ref "C52") (pin "2") (pinfunction "2_2") (pintype "passive"))
      (node (ref "C53") (pin "1") (pinfunction "1_1") (pintype "passive"))
      (node (ref "C54") (pin "2") (pinfunction "2_2") (pintype "passive"))
      (node (ref "C55") (pin "2") (pinfunction "2_2") (pintype "passive"))
      (node (ref "C56") (pin "2") (pinfunction "2_2") (pintype "passive"))
      (node (ref "C57") (pin "2") (pinfunction "2_2") (pintype "passive"))
      (node (ref "C59") (pin "2") (pinfunction "2_2") (pintype "passive"))
      (node (ref "C6") (pin "1") (pinfunction "1_1") (pintype "passive"))
      (node (ref "C62") (pin "2") (pinfunction "2_2") (pintype "passive"))
      (node (ref "C63") (pin "2") (pinfunction "2_2") (pintype "passive"))
      (node (ref "C64") (pin "2") (pinfunction "2_2") (pintype "passive"))
      (node (ref "C65") (pin "2") (pinfunction "2_2") (pintype "passive"))
      (node (ref "C66") (pin "2") (pinfunction "2_2") (pintype "passive"))
      (node (ref "C67") (pin "1") (pinfunction "1_1") (pintype "passive"))
      (node (ref "C68") (pin "2") (pinfunction "2_2") (pintype "passive"))
      (node (ref "C69") (pin "2") (pinfunction "2_2") (pintype "passive"))
      (node (ref "C7") (pin "1") (pinfunction "1_1") (pintype "passive"))
      (node (ref "C70") (pin "2") (pinfunction "2_2") (pintype "passive"))
      (node (ref "C71") (pin "2") (pinfunction "2_2") (pintype "passive"))
      (node (ref "C73") (pin "2") (pinfunction "2_2") (pintype "passive"))
      (node (ref "C74") (pin "2") (pinfunction "2_2") (pintype "passive"))
      (node (ref "C75") (pin "2") (pinfunction "2_2") (pintype "passive"))
      (node (ref "C76") (pin "2") (pinfunction "2_2") (pintype "passive"))
      (node (ref "C77") (pin "1") (pinfunction "1_1") (pintype "passive"))
      (node (ref "C78") (pin "2") (pinfunction "2_2") (pintype "passive"))
      (node (ref "C79") (pin "2") (pinfunction "2_2") (pintype "passive"))
      (node (ref "C8") (pin "1") (pinfunction "1_1") (pintype "passive"))
      (node (ref "C80") (pin "2") (pinfunction "2_2") (pintype "passive"))
      (node (ref "C81") (pin "2") (pinfunction "2_2") (pintype "passive"))
      (node (ref "C82") (pin "2") (pinfunction "2_2") (pintype "passive"))
      (node (ref "C83") (pin "2") (pinfunction "2_2") (pintype "passive"))
      (node (ref "C86") (pin "2") (pinfunction "2_2") (pintype "passive"))
      (node (ref "C87") (pin "2") (pinfunction "2_2") (pintype "passive"))
      (node (ref "C88") (pin "2") (pinfunction "2_2") (pintype "passive"))
      (node (ref "C89") (pin "2") (pinfunction "2_2") (pintype "passive"))
      (node (ref "U1") (pin "A1") (pinfunction "GND_A1") (pintype "power_in"))
      (node (ref "U1") (pin "A2") (pinfunction "GND_A2") (pintype "power_in"))
      (node (ref "U1") (pin "A21") (pinfunction "GND_A21") (pintype "power_in"))
      (node (ref "U1") (pin "A22") (pinfunction "GND_A22") (pintype "power_in"))
      (node (ref "U1") (pin "AA1") (pinfunction "GND_AA1") (pintype "power_in"))
      (node (ref "U1") (pin "AA22") (pinfunction "GND_AA22") (pintype "power_in"))
      (node (ref "U1") (pin "AB1") (pinfunction "GND_AB1") (pintype "power_in"))
      (node (ref "U1") (pin "AB2") (pinfunction "GND_AB2") (pintype "power_in"))
      (node (ref "U1") (pin "AB21") (pinfunction "GND_AB21") (pintype "power_in"))
      (node (ref "U1") (pin "AB22") (pinfunction "GND_AB22") (pintype "power_in"))
      (node (ref "U1") (pin "B1") (pinfunction "GND_B1") (pintype "power_in"))
      (node (ref "U1") (pin "B22") (pinfunction "GND_B22") (pintype "power_in"))
      (node (ref "U1") (pin "C18") (pinfunction "GND_C18") (pintype "power_in"))
      (node (ref "U1") (pin "C5") (pinfunction "GND_C5") (pintype "power_in"))
      (node (ref "U1") (pin "D19") (pinfunction "GND_D19") (pintype "power_in"))
      (node (ref "U1") (pin "D4") (pinfunction "GND_D4") (pintype "power_in"))
      (node (ref "U1") (pin "E20") (pinfunction "GND_E20") (pintype "power_in"))
      (node (ref "U1") (pin "E3") (pinfunction "GND_E3") (pintype "power_in"))
      (node (ref "U1") (pin "E6") (pinfunction "GNDQ_E6") (pintype "power_in"))
      (node (ref "U1") (pin "G15") (pinfunction "GNDQ_G15") (pintype "power_in"))
      (node (ref "U1") (pin "G8") (pinfunction "GNDQ_G8") (pintype "power_in"))
      (node (ref "U1") (pin "J14") (pinfunction "GND_J14") (pintype "power_in"))
      (node (ref "U1") (pin "J9") (pinfunction "GND_J9") (pintype "power_in"))
      (node (ref "U1") (pin "K10") (pinfunction "GND_K10") (pintype "power_in"))
      (node (ref "U1") (pin "K11") (pinfunction "GND_K11") (pintype "power_in"))
      (node (ref "U1") (pin "K12") (pinfunction "GND_K12") (pintype "power_in"))
      (node (ref "U1") (pin "K13") (pinfunction "GND_K13") (pintype "power_in"))
      (node (ref "U1") (pin "L10") (pinfunction "GND_L10") (pintype "power_in"))
      (node (ref "U1") (pin "L11") (pinfunction "GND_L11") (pintype "power_in"))
      (node (ref "U1") (pin "L12") (pinfunction "GND_L12") (pintype "power_in"))
      (node (ref "U1") (pin "L13") (pinfunction "GND_L13") (pintype "power_in"))
      (node (ref "U1") (pin "L7") (pinfunction "VCOMPLF_L7") (pintype "power_in"))
      (node (ref "U1") (pin "M10") (pinfunction "GND_M10") (pintype "power_in"))
      (node (ref "U1") (pin "M11") (pinfunction "GND_M11") (pintype "power_in"))
      (node (ref "U1") (pin "M12") (pinfunction "GND_M12") (pintype "power_in"))
      (node (ref "U1") (pin "M13") (pinfunction "GND_M13") (pintype "power_in"))
      (node (ref "U1") (pin "N10") (pinfunction "GND_N10") (pintype "power_in"))
      (node (ref "U1") (pin "N11") (pinfunction "GND_N11") (pintype "power_in"))
      (node (ref "U1") (pin "N12") (pinfunction "GND_N12") (pintype "power_in"))
      (node (ref "U1") (pin "N13") (pinfunction "GND_N13") (pintype "power_in"))
      (node (ref "U1") (pin "P14") (pinfunction "GND_P14") (pintype "power_in"))
      (node (ref "U1") (pin "P9") (pinfunction "GND_P9") (pintype "power_in"))
      (node (ref "U1") (pin "T15") (pinfunction "GNDQ_T15") (pintype "power_in"))
      (node (ref "U1") (pin "T8") (pinfunction "GNDQ_T8") (pintype "power_in"))
      (node (ref "U1") (pin "V18") (pinfunction "GNDQ_V18") (pintype "power_in"))
      (node (ref "U1") (pin "V20") (pinfunction "GND_V20") (pintype "power_in"))
      (node (ref "U1") (pin "V3") (pinfunction "GND_V3") (pintype "power_in"))
      (node (ref "U1") (pin "W19") (pinfunction "GND_W19") (pintype "power_in"))
      (node (ref "U1") (pin "W4") (pinfunction "GND_W4") (pintype "power_in"))
      (node (ref "U1") (pin "Y18") (pinfunction "GND_Y18") (pintype "power_in"))
      (node (ref "U1") (pin "Y5") (pinfunction "GND_Y5") (pintype "power_in"))
    )
    (net (code "4") (name "VPLL") (class "Default")
      (node (ref "C6") (pin "2") (pinfunction "2_2") (pintype "passive"))
      (node (ref "C7") (pin "2") (pinfunction "2_2") (pintype "passive"))
      (node (ref "C8") (pin "2") (pinfunction "2_2") (pintype "passive"))
      (node (ref "L2") (pin "1") (pinfunction "1_1") (pintype "passive"))
      (node (ref "U1") (pin "M6") (pinfunction "VCCPLF_M6") (pintype "power_in"))
    )
  )
)
